# M.net
KiCad netlist of a schematic drawn in Altium Designer
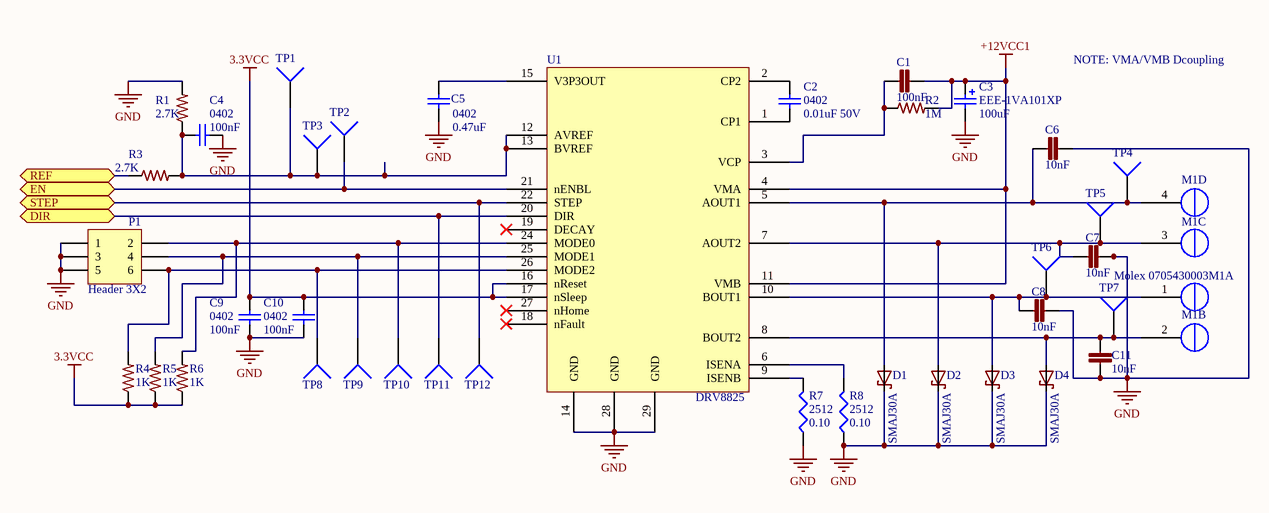
[diagram p0: M.SchDoc]

(export (version "E")
  (design (tool "Eeschema 10.0.6"))
  (components
    (comp (ref "C1")
      (value "100nF")
      (footprint "C0603")
      (description "CAP CER 0603 100nF 50V 10% X7R")
      (fields
        (field (name "MANUFACTURERPARTNUMBER") "C0603C104K5RACTU")
        (field (name "PUBLISHER") "UltiMachine")
      )
      (libsource (lib "3Delight") (part "C0603C104K5RACTU"))
    )
    (comp (ref "C2")
      (value "0.01uF 50V")
      (footprint "C0402")
      (description "CAP CER 10000PF 50V X7R 0402")
      (fields
        (field (name "MFR PART #") "GRM155R71H103JA88D")
        (field (name "MFR") "Murata")
        (field (name "PACKAGEREFERENCE") "0402")
        (field (name "PUBLISHER") "Ultimachine")
      )
      (libsource (lib "Tigershark3D") (part "GRM155R71H103JA88D"))
    )
    (comp (ref "C3")
      (value "EEE-1VA101XP")
      (footprint "EEE-1VA101XP")
      (description "CAP ALUM 100UF 35V 20% SMD")
      (fields (field (name "DIGIKEY PART #") "PCE3951CT-ND") (field (name "ALTIUM_VALUE") "100uF"))
      (libsource (lib "Tigershark3D") (part "EEE-1VA101XP"))
    )
    (comp (ref "C4")
      (value "100nF")
      (footprint "C0402")
      (description "Capacitor (Semiconductor SIM Model)")
      (fields
        (field (name "MFR PART #") "GRM155R71C104KA88D")
        (field (name "MFR") "Murata")
        (field (name "PACKAGEREFERENCE") "0402")
        (field (name "PUBLISHER") "Ultimachine")
      )
      (libsource (lib "Tigershark3D") (part "100nF C0402 - GRM155R71C104KA88D"))
    )
    (comp (ref "C5")
      (value "0.47uF")
      (footprint "C0402")
      (description "0.47uF 6.3v C0402 - GRM155R60J474KE19D")
      (fields
        (field (name "MFR PART #") "GRM155R60J474KE19D")
        (field (name "MFR") "Murata")
        (field (name "PACKAGEREFERENCE") "0402")
        (field (name "PUBLISHER") "Ultimachine")
      )
      (libsource (lib "Tigershark3D") (part "GRM155R60J474KE19D"))
    )
    (comp (ref "C6")
      (value "10nF")
      (footprint "C0603")
      (description "CAP CER 0603 10nF 25V 10% X7R")
      (fields
        (field (name "MANUFACTURERPARTNUMBER") "C1608X7R1E103K080AA")
        (field (name "PUBLISHER") "UltiMachine")
      )
      (libsource (lib "") (part "C1608X7R1E103K080AA_1"))
    )
    (comp (ref "C7")
      (value "10nF")
      (footprint "C0603")
      (description "CAP CER 0603 10nF 25V 10% X7R")
      (fields
        (field (name "MANUFACTURERPARTNUMBER") "C1608X7R1E103K080AA")
        (field (name "PUBLISHER") "UltiMachine")
      )
      (libsource (lib "") (part "C1608X7R1E103K080AA_1"))
    )
    (comp (ref "C8")
      (value "10nF")
      (footprint "C0603")
      (description "CAP CER 0603 10nF 25V 10% X7R")
      (fields
        (field (name "MANUFACTURERPARTNUMBER") "C1608X7R1E103K080AA")
        (field (name "PUBLISHER") "UltiMachine")
      )
      (libsource (lib "") (part "C1608X7R1E103K080AA_1"))
    )
    (comp (ref "C9")
      (value "100nF")
      (footprint "C0402")
      (description "Capacitor (Semiconductor SIM Model)")
      (fields
        (field (name "MFR PART #") "GRM155R71C104KA88D")
        (field (name "MFR") "Murata")
        (field (name "PACKAGEREFERENCE") "0402")
        (field (name "PUBLISHER") "Ultimachine")
      )
      (libsource (lib "Tigershark3D") (part "100nF C0402 - GRM155R71C104KA88D"))
    )
    (comp (ref "C10")
      (value "100nF")
      (footprint "C0402")
      (description "Capacitor (Semiconductor SIM Model)")
      (fields
        (field (name "MFR PART #") "GRM155R71C104KA88D")
        (field (name "MFR") "Murata")
        (field (name "PACKAGEREFERENCE") "0402")
        (field (name "PUBLISHER") "Ultimachine")
      )
      (libsource (lib "Tigershark3D") (part "100nF C0402 - GRM155R71C104KA88D"))
    )
    (comp (ref "C11")
      (value "10nF")
      (footprint "C0603")
      (description "CAP CER 0603 10nF 25V 10% X7R")
      (fields
        (field (name "MANUFACTURERPARTNUMBER") "C1608X7R1E103K080AA")
        (field (name "PUBLISHER") "UltiMachine")
      )
      (libsource (lib "3Delight") (part "C1608X7R1E103K080AA"))
    )
    (comp (ref "D1")
      (value "SMAJ30A")
      (footprint "SMA-SM")
      (description "DIODE TVS 30V SMA")
      (fields (field (name "PUBLISHER") "UltiMachine"))
      (libsource (lib "Tigershark3D") (part "SMAJ30A"))
    )
    (comp (ref "D2")
      (value "SMAJ30A")
      (footprint "SMA-SM")
      (description "DIODE TVS 30V SMA")
      (fields (field (name "PUBLISHER") "UltiMachine"))
      (libsource (lib "Tigershark3D") (part "SMAJ30A"))
    )
    (comp (ref "D3")
      (value "SMAJ30A")
      (footprint "SMA-SM")
      (description "DIODE TVS 30V SMA")
      (fields (field (name "PUBLISHER") "UltiMachine"))
      (libsource (lib "Tigershark3D") (part "SMAJ30A"))
    )
    (comp (ref "D4")
      (value "SMAJ30A")
      (footprint "SMA-SM")
      (description "DIODE TVS 30V SMA")
      (fields (field (name "PUBLISHER") "UltiMachine"))
      (libsource (lib "Tigershark3D") (part "SMAJ30A"))
    )
    (comp (ref "M1")
      (value "Molex 0705430003")
      (footprint "4POL254")
      (description "Molex 4 Pin Clip Connector")
      (libsource (lib "ZMBo Schematic Library") (part "Molex 0705430003 Alt"))
    )
    (comp (ref "P1")
      (value "Header 3X2")
      (footprint "HDR2X3")
      (description "Header, 3-Pin, Dual row")
      (fields (field (name "PUBLISHER") "Altium Limited"))
      (libsource (lib "Miscellaneous Connectors") (part "Header 3X2"))
    )
    (comp (ref "R1")
      (value "2.7K")
      (footprint "R0402")
      (description "RES SMD 2.7K OHM 1% 1/10W 0402")
      (fields
        (field (name "MANUFACTURER") "Panasonic")
        (field (name "MANUFACTURERPARTNUMBER") "ERJ2GEJ105X")
        (field (name "PUBLISHER") "Adam")
      )
      (libsource (lib "Tigershark3D") (part "ERJ-2RKF2701X"))
    )
    (comp (ref "R2")
      (value "1M")
      (footprint "R0402")
      (description "RES 0402 1M 100mW 5%")
      (fields (field (name "MANUFACTURERPARTNUMBER") "ERJ2GEJ105X") (field (name "PUBLISHER") "UltiMachine"))
      (libsource (lib "Tigershark3D") (part "ERJ2GEJ105X"))
    )
    (comp (ref "R3")
      (value "2.7K")
      (footprint "R0402")
      (description "RES SMD 2.7K OHM 1% 1/10W 0402")
      (fields
        (field (name "MANUFACTURER") "Panasonic")
        (field (name "MANUFACTURERPARTNUMBER") "ERJ2GEJ105X")
        (field (name "PUBLISHER") "Adam")
      )
      (libsource (lib "Tigershark3D") (part "ERJ-2RKF2701X"))
    )
    (comp (ref "R4")
      (value "1K")
      (footprint "R0603")
      (description "RES 0603 1K 100mW 1%")
      (fields
        (field (name "MANUFACTURERPARTNUMBER") "ERJ-3EKF1001V")
        (field (name "PUBLISHER") "UltiMachine")
      )
      (libsource (lib "3Delight") (part "ERJ-3EKF1001V"))
    )
    (comp (ref "R5")
      (value "1K")
      (footprint "R0603")
      (description "RES 0603 1K 100mW 1%")
      (fields
        (field (name "MANUFACTURERPARTNUMBER") "ERJ-3EKF1001V")
        (field (name "PUBLISHER") "UltiMachine")
      )
      (libsource (lib "3Delight") (part "ERJ-3EKF1001V"))
    )
    (comp (ref "R6")
      (value "1K")
      (footprint "R0603")
      (description "RES 0603 1K 100mW 1%")
      (fields
        (field (name "MANUFACTURERPARTNUMBER") "ERJ-3EKF1001V")
        (field (name "PUBLISHER") "UltiMachine")
      )
      (libsource (lib "3Delight") (part "ERJ-3EKF1001V"))
    )
    (comp (ref "R7")
      (value "2512")
      (footprint "2512R-0.55")
      (description "RES SMD 0.1 OHM 1% 2W 2512")
      (fields (field (name "MFR") "Stackpole ELectronics Inc") (field (name "ALTIUM_VALUE") "0.10"))
      (libsource (lib "Tigershark3D") (part "CSRN2512FTR100"))
    )
    (comp (ref "R8")
      (value "2512")
      (footprint "2512R-0.55")
      (description "RES SMD 0.1 OHM 1% 2W 2512")
      (fields (field (name "MFR") "Stackpole ELectronics Inc") (field (name "ALTIUM_VALUE") "0.10"))
      (libsource (lib "Tigershark3D") (part "CSRN2512FTR100"))
    )
    (comp (ref "TP1")
      (value "TP4")
      (footprint "TP-2")
      (description "Socket")
      (fields (field (name "PUBLISHER") "Altium Limited"))
      (libsource (lib "ZMBo Schematic Library") (part "Socket"))
    )
    (comp (ref "TP2")
      (value "TP4")
      (footprint "TP-2")
      (description "Socket")
      (fields (field (name "PUBLISHER") "Altium Limited"))
      (libsource (lib "ZMBo Schematic Library") (part "Socket"))
    )
    (comp (ref "TP3")
      (value "TP4")
      (footprint "TP-2")
      (description "Socket")
      (fields (field (name "PUBLISHER") "Altium Limited"))
      (libsource (lib "ZMBo Schematic Library") (part "Socket"))
    )
    (comp (ref "TP4")
      (value "TP4")
      (footprint "TP-2")
      (description "Socket")
      (fields (field (name "PUBLISHER") "Altium Limited"))
      (libsource (lib "ZMBo Schematic Library") (part "Socket"))
    )
    (comp (ref "TP5")
      (value "TP4")
      (footprint "TP-2")
      (description "Socket")
      (fields (field (name "PUBLISHER") "Altium Limited"))
      (libsource (lib "ZMBo Schematic Library") (part "Socket"))
    )
    (comp (ref "TP6")
      (value "TP4")
      (footprint "TP-2")
      (description "Socket")
      (fields (field (name "PUBLISHER") "Altium Limited"))
      (libsource (lib "ZMBo Schematic Library") (part "Socket"))
    )
    (comp (ref "TP7")
      (value "TP4")
      (footprint "TP-2")
      (description "Socket")
      (fields (field (name "PUBLISHER") "Altium Limited"))
      (libsource (lib "ZMBo Schematic Library") (part "Socket"))
    )
    (comp (ref "TP8")
      (value "TP4")
      (footprint "TP-2")
      (description "Socket")
      (fields (field (name "PUBLISHER") "Altium Limited"))
      (libsource (lib "ZMBo Schematic Library") (part "Socket"))
    )
    (comp (ref "TP9")
      (value "TP4")
      (footprint "TP-2")
      (description "Socket")
      (fields (field (name "PUBLISHER") "Altium Limited"))
      (libsource (lib "ZMBo Schematic Library") (part "Socket"))
    )
    (comp (ref "TP10")
      (value "TP4")
      (footprint "TP-2")
      (description "Socket")
      (fields (field (name "PUBLISHER") "Altium Limited"))
      (libsource (lib "ZMBo Schematic Library") (part "Socket"))
    )
    (comp (ref "TP11")
      (value "TP4")
      (footprint "TP-2")
      (description "Socket")
      (fields (field (name "PUBLISHER") "Altium Limited"))
      (libsource (lib "ZMBo Schematic Library") (part "Socket"))
    )
    (comp (ref "TP12")
      (value "TP4")
      (footprint "TP-2")
      (description "Socket")
      (fields (field (name "PUBLISHER") "Altium Limited"))
      (libsource (lib "ZMBo Schematic Library") (part "Socket"))
    )
    (comp (ref "U1")
      (value "DRV8825")
      (footprint "DRV8825")
      (description "DRV8825 Ti Stepper Driver")
      (libsource (lib "ZMBo Schematic Library") (part "DRV8825"))
    )
  )
  (nets
    (net (code "1") (name "+12VCC1") (class "Default")
      (node (ref "C1") (pin "2") (pinfunction "2_2") (pintype "passive"))
      (node (ref "C3") (pin "1") (pinfunction "1_1") (pintype "passive"))
      (node (ref "R2") (pin "2") (pinfunction "2_2") (pintype "passive"))
      (node (ref "U1") (pin "11") (pinfunction "VMB_11") (pintype "passive"))
      (node (ref "U1") (pin "4") (pinfunction "VMA_4") (pintype "passive"))
    )
    (net (code "2") (name "/DIR") (class "Default")
      (node (ref "TP11") (pin "1") (pinfunction "1_1") (pintype "passive"))
      (node (ref "U1") (pin "20") (pinfunction "DIR_20") (pintype "passive"))
    )
    (net (code "3") (name "/EN") (class "Default")
      (node (ref "TP2") (pin "1") (pinfunction "1_1") (pintype "passive"))
      (node (ref "U1") (pin "21") (pinfunction "nENBL_21") (pintype "passive"))
    )
    (net (code "4") (name "/REF") (class "Default")
      (node (ref "R3") (pin "1") (pinfunction "1_1") (pintype "passive"))
    )
    (net (code "5") (name "/STEP") (class "Default")
      (node (ref "TP12") (pin "1") (pinfunction "1_1") (pintype "passive"))
      (node (ref "U1") (pin "22") (pinfunction "STEP_22") (pintype "passive"))
    )
    (net (code "6") (name "3.3VCC") (class "Default")
      (node (ref "C10") (pin "2") (pinfunction "2_2") (pintype "passive"))
      (node (ref "C9") (pin "2") (pinfunction "2_2") (pintype "passive"))
      (node (ref "R4") (pin "1") (pinfunction "1_1") (pintype "passive"))
      (node (ref "R5") (pin "1") (pinfunction "1_1") (pintype "passive"))
      (node (ref "R6") (pin "1") (pinfunction "1_1") (pintype "passive"))
      (node (ref "U1") (pin "16") (pinfunction "nReset_16") (pintype "passive"))
      (node (ref "U1") (pin "17") (pinfunction "nSleep_17") (pintype "passive"))
    )
    (net (code "7") (name "GND") (class "Default")
      (node (ref "C10") (pin "1") (pinfunction "1_1") (pintype "passive"))
      (node (ref "C11") (pin "1") (pinfunction "1_1") (pintype "passive"))
      (node (ref "C3") (pin "2") (pinfunction "2_2") (pintype "passive"))
      (node (ref "C4") (pin "1") (pinfunction "1_1") (pintype "passive"))
      (node (ref "C5") (pin "1") (pinfunction "1_1") (pintype "passive"))
      (node (ref "C6") (pin "2") (pinfunction "2_2") (pintype "passive"))
      (node (ref "C7") (pin "2") (pinfunction "2_2") (pintype "passive"))
      (node (ref "C8") (pin "2") (pinfunction "2_2") (pintype "passive"))
      (node (ref "C9") (pin "1") (pinfunction "1_1") (pintype "passive"))
      (node (ref "D1") (pin "C") (pinfunction "C_C") (pintype "passive"))
      (node (ref "D2") (pin "C") (pinfunction "C_C") (pintype "passive"))
      (node (ref "D3") (pin "C") (pinfunction "C_C") (pintype "passive"))
      (node (ref "D4") (pin "C") (pinfunction "C_C") (pintype "passive"))
      (node (ref "P1") (pin "1") (pinfunction "1_1") (pintype "passive"))
      (node (ref "P1") (pin "3") (pinfunction "3_3") (pintype "passive"))
      (node (ref "P1") (pin "5") (pinfunction "5_5") (pintype "passive"))
      (node (ref "R1") (pin "2") (pinfunction "2_2") (pintype "passive"))
      (node (ref "R7") (pin "1") (pinfunction "1_1") (pintype "passive"))
      (node (ref "R8") (pin "1") (pinfunction "1_1") (pintype "passive"))
      (node (ref "U1") (pin "14") (pinfunction "GND_14") (pintype "passive"))
      (node (ref "U1") (pin "28") (pinfunction "GND_28") (pintype "passive"))
      (node (ref "U1") (pin "29") (pinfunction "GND_29") (pintype "passive"))
    )
    (net (code "8") (name "Net-(M1A-OUT2B)") (class "Default")
      (node (ref "C8") (pin "1") (pinfunction "1_1") (pintype "passive"))
      (node (ref "D3") (pin "A") (pinfunction "A_A") (pintype "passive"))
      (node (ref "M1") (pin "1") (pinfunction "OUT2B_1") (pintype "passive"))
      (node (ref "TP6") (pin "1") (pinfunction "1_1") (pintype "passive"))
      (node (ref "U1") (pin "10") (pinfunction "BOUT1_10") (pintype "passive"))
    )
    (net (code "9") (name "Net-(M1B-OUT2A)") (class "Default")
      (node (ref "C11") (pin "2") (pinfunction "2_2") (pintype "passive"))
      (node (ref "D4") (pin "A") (pinfunction "A_A") (pintype "passive"))
      (node (ref "M1") (pin "2") (pinfunction "OUT2A_2") (pintype "passive"))
      (node (ref "TP7") (pin "1") (pinfunction "1_1") (pintype "passive"))
      (node (ref "U1") (pin "8") (pinfunction "BOUT2_8") (pintype "passive"))
    )
    (net (code "10") (name "Net-(M1C-OUT1A)") (class "Default")
      (node (ref "C7") (pin "1") (pinfunction "1_1") (pintype "passive"))
      (node (ref "D2") (pin "A") (pinfunction "A_A") (pintype "passive"))
      (node (ref "M1") (pin "3") (pinfunction "OUT1A_3") (pintype "passive"))
      (node (ref "TP5") (pin "1") (pinfunction "1_1") (pintype "passive"))
      (node (ref "U1") (pin "7") (pinfunction "AOUT2_7") (pintype "passive"))
    )
    (net (code "11") (name "Net-(M1D-OUT1B)") (class "Default")
      (node (ref "C6") (pin "1") (pinfunction "1_1") (pintype "passive"))
      (node (ref "D1") (pin "A") (pinfunction "A_A") (pintype "passive"))
      (node (ref "M1") (pin "4") (pinfunction "OUT1B_4") (pintype "passive"))
      (node (ref "TP4") (pin "1") (pinfunction "1_1") (pintype "passive"))
      (node (ref "U1") (pin "5") (pinfunction "AOUT1_5") (pintype "passive"))
    )
    (net (code "12") (name "Net-(U1-AVREF)") (class "Default")
      (node (ref "C4") (pin "2") (pinfunction "2_2") (pintype "passive"))
      (node (ref "R1") (pin "1") (pinfunction "1_1") (pintype "passive"))
      (node (ref "R3") (pin "2") (pinfunction "2_2") (pintype "passive"))
      (node (ref "TP1") (pin "1") (pinfunction "1_1") (pintype "passive"))
      (node (ref "TP3") (pin "1") (pinfunction "1_1") (pintype "passive"))
      (node (ref "U1") (pin "12") (pinfunction "AVREF_12") (pintype "passive"))
      (node (ref "U1") (pin "13") (pinfunction "BVREF_13") (pintype "passive"))
    )
    (net (code "13") (name "Net-(U1-CP1)") (class "Default")
      (node (ref "C2") (pin "1") (pinfunction "1_1") (pintype "passive"))
      (node (ref "U1") (pin "1") (pinfunction "CP1_1") (pintype "passive"))
    )
    (net (code "14") (name "Net-(U1-CP2)") (class "Default")
      (node (ref "C2") (pin "2") (pinfunction "2_2") (pintype "passive"))
      (node (ref "U1") (pin "2") (pinfunction "CP2_2") (pintype "passive"))
    )
    (net (code "15") (name "Net-(U1-ISENA)") (class "Default")
      (node (ref "R8") (pin "2") (pinfunction "2_2") (pintype "passive"))
      (node (ref "U1") (pin "6") (pinfunction "ISENA_6") (pintype "passive"))
    )
    (net (code "16") (name "Net-(U1-ISENB)") (class "Default")
      (node (ref "R7") (pin "2") (pinfunction "2_2") (pintype "passive"))
      (node (ref "U1") (pin "9") (pinfunction "ISENB_9") (pintype "passive"))
    )
    (net (code "17") (name "Net-(U1-MODE0)") (class "Default")
      (node (ref "P1") (pin "2") (pinfunction "2_2") (pintype "passive"))
      (node (ref "R6") (pin "2") (pinfunction "2_2") (pintype "passive"))
      (node (ref "TP10") (pin "1") (pinfunction "1_1") (pintype "passive"))
      (node (ref "U1") (pin "24") (pinfunction "MODE0_24") (pintype "passive"))
    )
    (net (code "18") (name "Net-(U1-MODE1)") (class "Default")
      (node (ref "P1") (pin "4") (pinfunction "4_4") (pintype "passive"))
      (node (ref "R5") (pin "2") (pinfunction "2_2") (pintype "passive"))
      (node (ref "TP9") (pin "1") (pinfunction "1_1") (pintype "passive"))
      (node (ref "U1") (pin "25") (pinfunction "MODE1_25") (pintype "passive"))
    )
    (net (code "19") (name "Net-(U1-MODE2)") (class "Default")
      (node (ref "P1") (pin "6") (pinfunction "6_6") (pintype "passive"))
      (node (ref "R4") (pin "2") (pinfunction "2_2") (pintype "passive"))
      (node (ref "TP8") (pin "1") (pinfunction "1_1") (pintype "passive"))
      (node (ref "U1") (pin "26") (pinfunction "MODE2_26") (pintype "passive"))
    )
    (net (code "20") (name "Net-(U1-V3P3OUT)") (class "Default")
      (node (ref "C5") (pin "2") (pinfunction "2_2") (pintype "passive"))
      (node (ref "U1") (pin "15") (pinfunction "V3P3OUT_15") (pintype "passive"))
    )
    (net (code "21") (name "Net-(U1-VCP)") (class "Default")
      (node (ref "C1") (pin "1") (pinfunction "1_1") (pintype "passive"))
      (node (ref "R2") (pin "1") (pinfunction "1_1") (pintype "passive"))
      (node (ref "U1") (pin "3") (pinfunction "VCP_3") (pintype "passive"))
    )
    (net (code "22") (name "unconnected-(U1-DECAY-Pad19)") (class "Default")
      (node (ref "U1") (pin "19") (pinfunction "DECAY_19") (pintype "passive+no_connect"))
    )
    (net (code "23") (name "unconnected-(U1-NC-Pad23)") (class "Default")
      (node (ref "U1") (pin "23") (pinfunction "NC_23") (pintype "passive"))
    )
    (net (code "24") (name "unconnected-(U1-nFault-Pad18)") (class "Default")
      (node (ref "U1") (pin "18") (pinfunction "nFault_18") (pintype "passive+no_connect"))
    )
    (net (code "25") (name "unconnected-(U1-nHome-Pad27)") (class "Default")
      (node (ref "U1") (pin "27") (pinfunction "nHome_27") (pintype "passive+no_connect"))
    )
  )
)
